# JW24A10L_revC.net
KiCad netlist of a schematic drawn in EAGLE
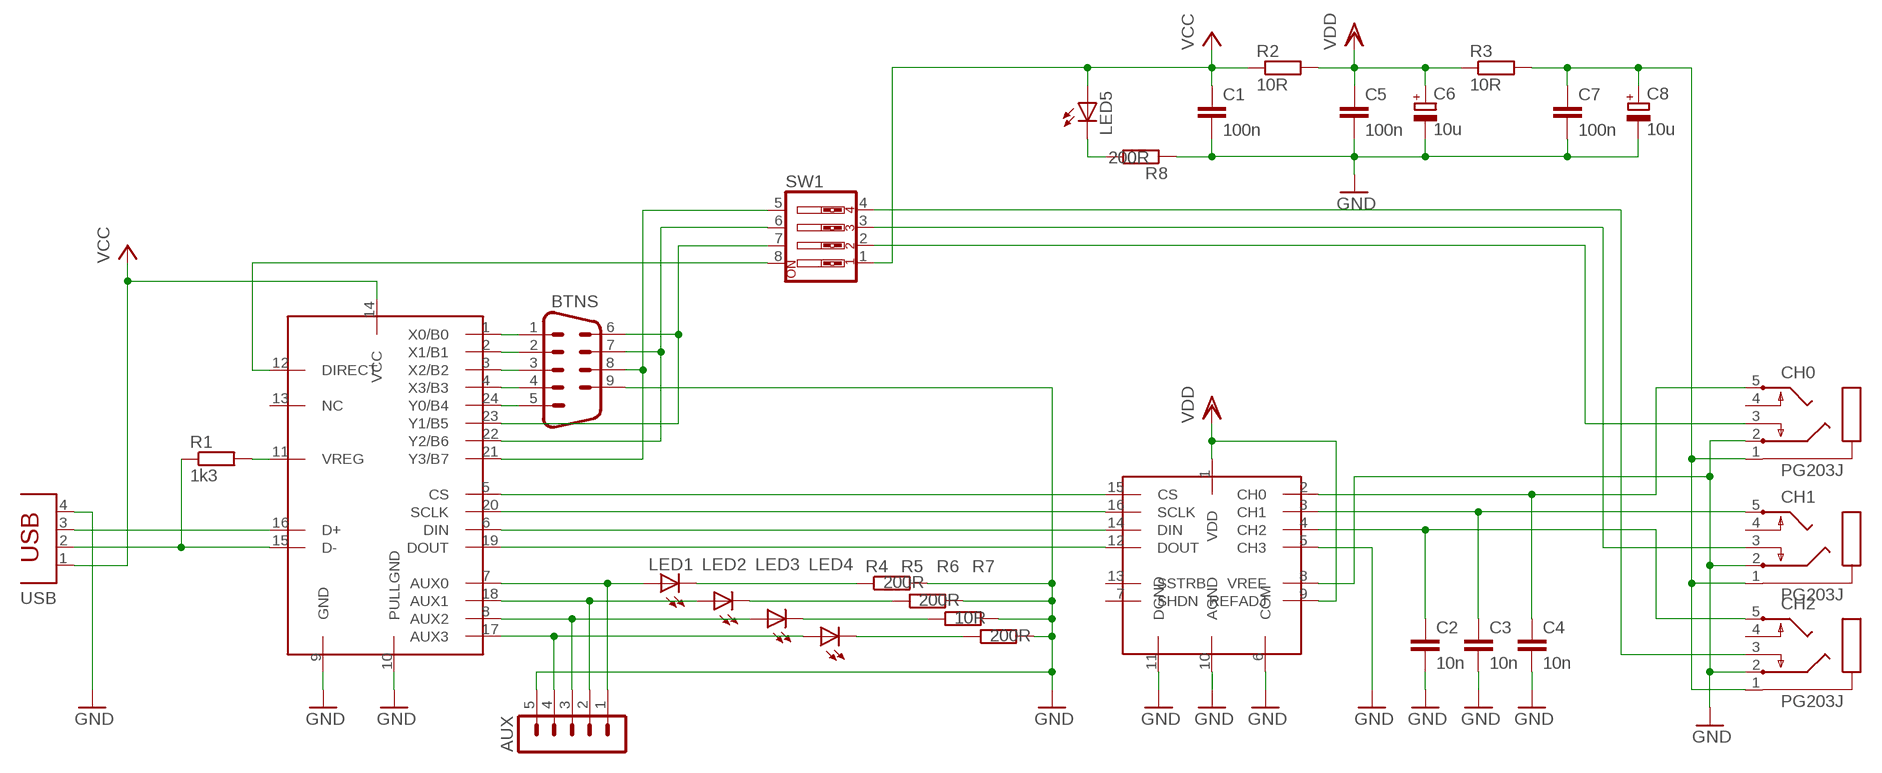
[diagram p0: schematic, sheet 1]

(export (version "E")
  (design (tool "Eeschema 10.0.6"))
  (components
    (comp (ref "AUX")
      (value "MA05-1")
      (footprint "eagle-import:MA05-1")
      (libsource (lib "eagle-import") (part "MA05-1"))
    )
    (comp (ref "BTNS")
      (value "M09H")
      (footprint "eagle-import:M09H")
      (libsource (lib "eagle-import") (part "M09H"))
    )
    (comp (ref "C1")
      (value "100n")
      (footprint "eagle-import:C025-025X050")
      (libsource (lib "eagle-import") (part "C-EU025-025X050"))
    )
    (comp (ref "C2")
      (value "10n")
      (footprint "eagle-import:C025-025X050")
      (libsource (lib "eagle-import") (part "C-EU025-025X050"))
    )
    (comp (ref "C3")
      (value "10n")
      (footprint "eagle-import:C025-025X050")
      (libsource (lib "eagle-import") (part "C-EU025-025X050"))
    )
    (comp (ref "C4")
      (value "10n")
      (footprint "eagle-import:C025-025X050")
      (libsource (lib "eagle-import") (part "C-EU025-025X050"))
    )
    (comp (ref "C5")
      (value "100n")
      (footprint "eagle-import:C025-025X050")
      (libsource (lib "eagle-import") (part "C-EU025-025X050"))
    )
    (comp (ref "C6")
      (value "10u")
      (footprint "eagle-import:E2-5")
      (libsource (lib "eagle-import") (part "CPOL-EUE2-5"))
    )
    (comp (ref "C7")
      (value "100n")
      (footprint "eagle-import:C025-025X050")
      (libsource (lib "eagle-import") (part "C-EU025-025X050"))
    )
    (comp (ref "C8")
      (value "10u")
      (footprint "eagle-import:E2-5")
      (libsource (lib "eagle-import") (part "CPOL-EUE2-5"))
    )
    (comp (ref "CH0")
      (value "PG203J")
      (footprint "eagle-import:PG203J")
      (libsource (lib "eagle-import") (part "PG203J"))
    )
    (comp (ref "CH1")
      (value "PG203J")
      (footprint "eagle-import:PG203J")
      (libsource (lib "eagle-import") (part "PG203J"))
    )
    (comp (ref "CH2")
      (value "PG203J")
      (footprint "eagle-import:PG203J")
      (libsource (lib "eagle-import") (part "PG203J"))
    )
    (comp (ref "LED1")
      (value "LED3MM")
      (footprint "eagle-import:LED3MM")
      (libsource (lib "eagle-import") (part "LED3MM"))
    )
    (comp (ref "LED2")
      (value "LED3MM")
      (footprint "eagle-import:LED3MM")
      (libsource (lib "eagle-import") (part "LED3MM"))
    )
    (comp (ref "LED3")
      (value "LED3MM")
      (footprint "eagle-import:LED3MM")
      (libsource (lib "eagle-import") (part "LED3MM"))
    )
    (comp (ref "LED4")
      (value "LED3MM")
      (footprint "eagle-import:LED3MM")
      (libsource (lib "eagle-import") (part "LED3MM"))
    )
    (comp (ref "LED5")
      (value "LED3MM")
      (footprint "eagle-import:LED3MM")
      (libsource (lib "eagle-import") (part "LED3MM"))
    )
    (comp (ref "R1")
      (value "1k3")
      (footprint "eagle-import:0204_7")
      (libsource (lib "eagle-import") (part "R-EU_0204/7"))
    )
    (comp (ref "R2")
      (value "10R")
      (footprint "eagle-import:0204_7")
      (libsource (lib "eagle-import") (part "R-EU_0204/7"))
    )
    (comp (ref "R3")
      (value "10R")
      (footprint "eagle-import:0204_7")
      (libsource (lib "eagle-import") (part "R-EU_0204/7"))
    )
    (comp (ref "R4")
      (value "200R")
      (footprint "eagle-import:0204_7")
      (libsource (lib "eagle-import") (part "R-EU_0204/7"))
    )
    (comp (ref "R5")
      (value "200R")
      (footprint "eagle-import:0204_7")
      (libsource (lib "eagle-import") (part "R-EU_0204/7"))
    )
    (comp (ref "R6")
      (value "10R")
      (footprint "eagle-import:0204_7")
      (libsource (lib "eagle-import") (part "R-EU_0204/7"))
    )
    (comp (ref "R7")
      (value "200R")
      (footprint "eagle-import:0204_7")
      (libsource (lib "eagle-import") (part "R-EU_0204/7"))
    )
    (comp (ref "R8")
      (value "200R")
      (footprint "eagle-import:0204_7")
      (libsource (lib "eagle-import") (part "R-EU_0204/7"))
    )
    (comp (ref "SW1")
      (value "SW_DIP-4")
      (footprint "eagle-import:EDG-04")
      (libsource (lib "eagle-import") (part "SW_DIP-4"))
    )
    (comp (ref "U$1")
      (value "MAX1249")
      (footprint "eagle-import:DIL16")
      (libsource (lib "eagle-import") (part "MAX1249"))
    )
    (comp (ref "U$2")
      (value "JW24A10L")
      (footprint "eagle-import:DIL24-3")
      (libsource (lib "eagle-import") (part "JW24A10L"))
    )
    (comp (ref "USB")
      (value "PN61729")
      (footprint "eagle-import:PN61729")
      (libsource (lib "eagle-import") (part "PN61729"))
    )
  )
  (nets
    (net (code "1") (name "GND") (class "Default")
      (node (ref "AUX") (pin "5") (pinfunction "5_5") (pintype "passive"))
      (node (ref "BTNS") (pin "9") (pinfunction "9_9") (pintype "passive"))
      (node (ref "C1") (pin "2") (pinfunction "2_2") (pintype "passive"))
      (node (ref "C2") (pin "2") (pinfunction "2_2") (pintype "passive"))
      (node (ref "C3") (pin "2") (pinfunction "2_2") (pintype "passive"))
      (node (ref "C4") (pin "2") (pinfunction "2_2") (pintype "passive"))
      (node (ref "C5") (pin "2") (pinfunction "2_2") (pintype "passive"))
      (node (ref "C6") (pin "-") (pinfunction "-_-") (pintype "passive"))
      (node (ref "C7") (pin "2") (pinfunction "2_2") (pintype "passive"))
      (node (ref "C8") (pin "-") (pinfunction "-_-") (pintype "passive"))
      (node (ref "CH0") (pin "2") (pinfunction "2_2") (pintype "passive"))
      (node (ref "CH1") (pin "2") (pinfunction "2_2") (pintype "passive"))
      (node (ref "CH2") (pin "2") (pinfunction "2_2") (pintype "passive"))
      (node (ref "R4") (pin "2") (pinfunction "2_2") (pintype "passive"))
      (node (ref "R5") (pin "2") (pinfunction "2_2") (pintype "passive"))
      (node (ref "R6") (pin "2") (pinfunction "2_2") (pintype "passive"))
      (node (ref "R7") (pin "2") (pinfunction "2_2") (pintype "passive"))
      (node (ref "R8") (pin "1") (pinfunction "1_1") (pintype "passive"))
      (node (ref "U$1") (pin "10") (pinfunction "AGND_10") (pintype "power_in"))
      (node (ref "U$1") (pin "11") (pinfunction "DGND_11") (pintype "power_in"))
      (node (ref "U$1") (pin "5") (pinfunction "CH3_5") (pintype "input"))
      (node (ref "U$1") (pin "6") (pinfunction "COM_6") (pintype "bidirectional"))
      (node (ref "U$1") (pin "8") (pinfunction "VREF_8") (pintype "bidirectional"))
      (node (ref "U$2") (pin "10") (pinfunction "PULLGND_10") (pintype "power_in"))
      (node (ref "U$2") (pin "9") (pinfunction "GND_9") (pintype "power_in"))
      (node (ref "USB") (pin "4") (pinfunction "4_4") (pintype "passive"))
    )
    (net (code "2") (name "Net-(C7-Pad1)") (class "Default")
      (node (ref "C7") (pin "1") (pinfunction "1_1") (pintype "passive"))
      (node (ref "C8") (pin "+") (pinfunction "+_+") (pintype "passive"))
      (node (ref "CH0") (pin "1") (pinfunction "1_1") (pintype "passive"))
      (node (ref "CH1") (pin "1") (pinfunction "1_1") (pintype "passive"))
      (node (ref "CH2") (pin "1") (pinfunction "1_1") (pintype "passive"))
      (node (ref "R3") (pin "2") (pinfunction "2_2") (pintype "passive"))
    )
    (net (code "3") (name "Net-(CH0-Pad3)") (class "Default")
      (node (ref "CH0") (pin "3") (pinfunction "3_3") (pintype "passive"))
      (node (ref "SW1") (pin "2") (pinfunction "2_2") (pintype "passive"))
    )
    (net (code "4") (name "Net-(CH1-Pad3)") (class "Default")
      (node (ref "CH1") (pin "3") (pinfunction "3_3") (pintype "passive"))
      (node (ref "SW1") (pin "3") (pinfunction "3_3") (pintype "passive"))
    )
    (net (code "5") (name "Net-(CH2-Pad3)") (class "Default")
      (node (ref "CH2") (pin "3") (pinfunction "3_3") (pintype "passive"))
      (node (ref "SW1") (pin "4") (pinfunction "4_4") (pintype "passive"))
    )
    (net (code "6") (name "Net-(LED1-C)") (class "Default")
      (node (ref "LED1") (pin "K") (pinfunction "C_K") (pintype "passive"))
      (node (ref "R4") (pin "1") (pinfunction "1_1") (pintype "passive"))
    )
    (net (code "7") (name "Net-(LED2-C)") (class "Default")
      (node (ref "LED2") (pin "K") (pinfunction "C_K") (pintype "passive"))
      (node (ref "R5") (pin "1") (pinfunction "1_1") (pintype "passive"))
    )
    (net (code "8") (name "Net-(LED3-C)") (class "Default")
      (node (ref "LED3") (pin "K") (pinfunction "C_K") (pintype "passive"))
      (node (ref "R6") (pin "1") (pinfunction "1_1") (pintype "passive"))
    )
    (net (code "9") (name "Net-(LED4-C)") (class "Default")
      (node (ref "LED4") (pin "K") (pinfunction "C_K") (pintype "passive"))
      (node (ref "R7") (pin "1") (pinfunction "1_1") (pintype "passive"))
    )
    (net (code "10") (name "Net-(LED5-C)") (class "Default")
      (node (ref "LED5") (pin "K") (pinfunction "C_K") (pintype "passive"))
      (node (ref "R8") (pin "2") (pinfunction "2_2") (pintype "passive"))
    )
    (net (code "11") (name "Net-(U$1-CH0)") (class "Default")
      (node (ref "C4") (pin "1") (pinfunction "1_1") (pintype "passive"))
      (node (ref "CH0") (pin "5") (pinfunction "5_5") (pintype "passive"))
      (node (ref "U$1") (pin "2") (pinfunction "CH0_2") (pintype "input"))
    )
    (net (code "12") (name "Net-(U$1-CH1)") (class "Default")
      (node (ref "C3") (pin "1") (pinfunction "1_1") (pintype "passive"))
      (node (ref "CH1") (pin "5") (pinfunction "5_5") (pintype "passive"))
      (node (ref "U$1") (pin "3") (pinfunction "CH1_3") (pintype "input"))
    )
    (net (code "13") (name "Net-(U$1-CH2)") (class "Default")
      (node (ref "C2") (pin "1") (pinfunction "1_1") (pintype "passive"))
      (node (ref "CH2") (pin "5") (pinfunction "5_5") (pintype "passive"))
      (node (ref "U$1") (pin "4") (pinfunction "CH2_4") (pintype "input"))
    )
    (net (code "14") (name "Net-(U$1-CS)") (class "Default")
      (node (ref "U$1") (pin "15") (pinfunction "CS_15") (pintype "bidirectional"))
      (node (ref "U$2") (pin "5") (pinfunction "CS_5") (pintype "bidirectional"))
    )
    (net (code "15") (name "Net-(U$1-DIN)") (class "Default")
      (node (ref "U$1") (pin "14") (pinfunction "DIN_14") (pintype "bidirectional"))
      (node (ref "U$2") (pin "6") (pinfunction "DIN_6") (pintype "bidirectional"))
    )
    (net (code "16") (name "Net-(U$1-DOUT)") (class "Default")
      (node (ref "U$1") (pin "12") (pinfunction "DOUT_12") (pintype "bidirectional"))
      (node (ref "U$2") (pin "19") (pinfunction "DOUT_19") (pintype "bidirectional"))
    )
    (net (code "17") (name "Net-(U$1-SCLK)") (class "Default")
      (node (ref "U$1") (pin "16") (pinfunction "SCLK_16") (pintype "bidirectional"))
      (node (ref "U$2") (pin "20") (pinfunction "SCLK_20") (pintype "bidirectional"))
    )
    (net (code "18") (name "Net-(U$2-AUX0)") (class "Default")
      (node (ref "AUX") (pin "1") (pinfunction "1_1") (pintype "passive"))
      (node (ref "LED1") (pin "A") (pinfunction "A_A") (pintype "passive"))
      (node (ref "U$2") (pin "7") (pinfunction "AUX0_7") (pintype "power_in"))
    )
    (net (code "19") (name "Net-(U$2-AUX1)") (class "Default")
      (node (ref "AUX") (pin "2") (pinfunction "2_2") (pintype "passive"))
      (node (ref "LED2") (pin "A") (pinfunction "A_A") (pintype "passive"))
      (node (ref "U$2") (pin "18") (pinfunction "AUX1_18") (pintype "power_in"))
    )
    (net (code "20") (name "Net-(U$2-AUX2)") (class "Default")
      (node (ref "AUX") (pin "3") (pinfunction "3_3") (pintype "passive"))
      (node (ref "LED3") (pin "A") (pinfunction "A_A") (pintype "passive"))
      (node (ref "U$2") (pin "8") (pinfunction "AUX2_8") (pintype "power_in"))
    )
    (net (code "21") (name "Net-(U$2-AUX3)") (class "Default")
      (node (ref "AUX") (pin "4") (pinfunction "4_4") (pintype "passive"))
      (node (ref "LED4") (pin "A") (pinfunction "A_A") (pintype "passive"))
      (node (ref "U$2") (pin "17") (pinfunction "AUX3_17") (pintype "power_in"))
    )
    (net (code "22") (name "Net-(U$2-D+)") (class "Default")
      (node (ref "U$2") (pin "16") (pinfunction "D+_16") (pintype "bidirectional"))
      (node (ref "USB") (pin "3") (pinfunction "3_3") (pintype "passive"))
    )
    (net (code "23") (name "Net-(U$2-D-)") (class "Default")
      (node (ref "R1") (pin "1") (pinfunction "1_1") (pintype "passive"))
      (node (ref "U$2") (pin "15") (pinfunction "D-_15") (pintype "bidirectional"))
      (node (ref "USB") (pin "2") (pinfunction "2_2") (pintype "passive"))
    )
    (net (code "24") (name "Net-(U$2-DIRECT)") (class "Default")
      (node (ref "SW1") (pin "8") (pinfunction "8_8") (pintype "passive"))
      (node (ref "U$2") (pin "12") (pinfunction "DIRECT_12") (pintype "bidirectional"))
    )
    (net (code "25") (name "Net-(U$2-VREG)") (class "Default")
      (node (ref "R1") (pin "2") (pinfunction "2_2") (pintype "passive"))
      (node (ref "U$2") (pin "11") (pinfunction "VREG_11") (pintype "bidirectional"))
    )
    (net (code "26") (name "Net-(U$2-X0{slash}B0)") (class "Default")
      (node (ref "BTNS") (pin "1") (pinfunction "1_1") (pintype "passive"))
      (node (ref "U$2") (pin "1") (pinfunction "X0/B0_1") (pintype "bidirectional"))
    )
    (net (code "27") (name "Net-(U$2-X1{slash}B1)") (class "Default")
      (node (ref "BTNS") (pin "2") (pinfunction "2_2") (pintype "passive"))
      (node (ref "U$2") (pin "2") (pinfunction "X1/B1_2") (pintype "bidirectional"))
    )
    (net (code "28") (name "Net-(U$2-X2{slash}B2)") (class "Default")
      (node (ref "BTNS") (pin "3") (pinfunction "3_3") (pintype "passive"))
      (node (ref "U$2") (pin "3") (pinfunction "X2/B2_3") (pintype "bidirectional"))
    )
    (net (code "29") (name "Net-(U$2-X3{slash}B3)") (class "Default")
      (node (ref "BTNS") (pin "4") (pinfunction "4_4") (pintype "passive"))
      (node (ref "U$2") (pin "4") (pinfunction "X3/B3_4") (pintype "bidirectional"))
    )
    (net (code "30") (name "Net-(U$2-Y0{slash}B4)") (class "Default")
      (node (ref "BTNS") (pin "5") (pinfunction "5_5") (pintype "passive"))
      (node (ref "U$2") (pin "24") (pinfunction "Y0/B4_24") (pintype "bidirectional"))
    )
    (net (code "31") (name "Net-(U$2-Y1{slash}B5)") (class "Default")
      (node (ref "BTNS") (pin "6") (pinfunction "6_6") (pintype "passive"))
      (node (ref "SW1") (pin "7") (pinfunction "7_7") (pintype "passive"))
      (node (ref "U$2") (pin "23") (pinfunction "Y1/B5_23") (pintype "bidirectional"))
    )
    (net (code "32") (name "Net-(U$2-Y2{slash}B6)") (class "Default")
      (node (ref "BTNS") (pin "7") (pinfunction "7_7") (pintype "passive"))
      (node (ref "SW1") (pin "6") (pinfunction "6_6") (pintype "passive"))
      (node (ref "U$2") (pin "22") (pinfunction "Y2/B6_22") (pintype "bidirectional"))
    )
    (net (code "33") (name "Net-(U$2-Y3{slash}B7)") (class "Default")
      (node (ref "BTNS") (pin "8") (pinfunction "8_8") (pintype "passive"))
      (node (ref "SW1") (pin "5") (pinfunction "5_5") (pintype "passive"))
      (node (ref "U$2") (pin "21") (pinfunction "Y3/B7_21") (pintype "bidirectional"))
    )
    (net (code "34") (name "VCC") (class "Default")
      (node (ref "C1") (pin "1") (pinfunction "1_1") (pintype "passive"))
      (node (ref "LED5") (pin "A") (pinfunction "A_A") (pintype "passive"))
      (node (ref "R2") (pin "1") (pinfunction "1_1") (pintype "passive"))
      (node (ref "SW1") (pin "1") (pinfunction "1_1") (pintype "passive"))
      (node (ref "U$2") (pin "14") (pinfunction "VCC_14") (pintype "power_in"))
      (node (ref "USB") (pin "1") (pinfunction "1_1") (pintype "passive"))
    )
    (net (code "35") (name "VDD") (class "Default")
      (node (ref "C5") (pin "1") (pinfunction "1_1") (pintype "passive"))
      (node (ref "C6") (pin "+") (pinfunction "+_+") (pintype "passive"))
      (node (ref "R2") (pin "2") (pinfunction "2_2") (pintype "passive"))
      (node (ref "R3") (pin "1") (pinfunction "1_1") (pintype "passive"))
      (node (ref "U$1") (pin "1") (pinfunction "VDD_1") (pintype "power_in"))
      (node (ref "U$1") (pin "9") (pinfunction "REFADJ_9") (pintype "bidirectional"))
    )
    (net (code "36") (name "unconnected-(CH0-Pad4)") (class "Default")
      (node (ref "CH0") (pin "4") (pinfunction "4_4") (pintype "passive"))
    )
    (net (code "37") (name "unconnected-(CH1-Pad4)") (class "Default")
      (node (ref "CH1") (pin "4") (pinfunction "4_4") (pintype "passive"))
    )
    (net (code "38") (name "unconnected-(CH2-Pad4)") (class "Default")
      (node (ref "CH2") (pin "4") (pinfunction "4_4") (pintype "passive"))
    )
    (net (code "39") (name "unconnected-(U$1-SHDN-Pad7)") (class "Default")
      (node (ref "U$1") (pin "7") (pinfunction "SHDN_7") (pintype "bidirectional"))
    )
    (net (code "40") (name "unconnected-(U$1-SSTRB-Pad13)") (class "Default")
      (node (ref "U$1") (pin "13") (pinfunction "SSTRB_13") (pintype "bidirectional"))
    )
    (net (code "41") (name "unconnected-(U$2-NC-Pad13)") (class "Default")
      (node (ref "U$2") (pin "13") (pinfunction "NC_13") (pintype "bidirectional"))
    )
  )
)
